# Throttle_Interfaces.net
KiCad netlist of a schematic drawn in Altium Designer
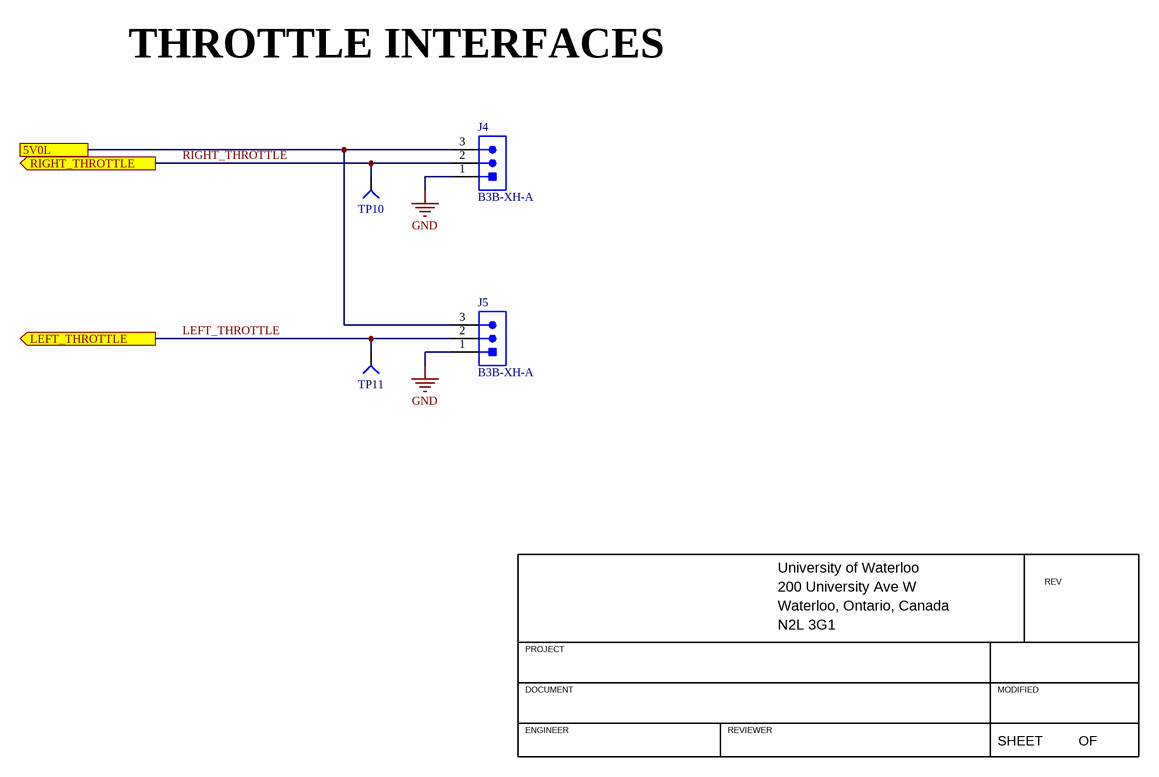
[diagram p0: Throttle Interfaces.SchDoc]

(export (version "E")
  (design (tool "Eeschema 10.0.6"))
  (components
    (comp (ref "J4")
      (value "CON_JST_3POS")
      (footprint "JST_XH_3POS")
      (description "CONN HEADER VERT 3POS 2.5MM")
      (fields (field (name "MANUFACTURER PART NUMBER 1") "B3B-XH-A"))
      (libsource (lib "Personal_Schematic_Library_2022") (part "CON_JST_3POS"))
    )
    (comp (ref "J5")
      (value "CON_JST_3POS")
      (footprint "JST_XH_3POS")
      (description "CONN HEADER VERT 3POS 2.5MM")
      (fields (field (name "MANUFACTURER PART NUMBER 1") "B3B-XH-A"))
      (libsource (lib "Personal_Schematic_Library_2022") (part "CON_JST_3POS"))
    )
    (comp (ref "TP10")
      (value "TESTPOINT_1MM_CIRCLE")
      (footprint "TESTPOINT_CIRCLE_1MM")
      (description "TESTPOINT 1MM CIRCLE")
      (libsource (lib "Personal_Schematic_Library_2022") (part "TESTPOINT_1MM_CIRCLE"))
    )
    (comp (ref "TP11")
      (value "TESTPOINT_1MM_CIRCLE")
      (footprint "TESTPOINT_CIRCLE_1MM")
      (description "TESTPOINT 1MM CIRCLE")
      (libsource (lib "Personal_Schematic_Library_2022") (part "TESTPOINT_1MM_CIRCLE"))
    )
  )
  (nets
    (net (code "1") (name "/5V0L") (class "Default")
      (node (ref "J4") (pin "3") (pinfunction "3_3") (pintype "passive"))
      (node (ref "J5") (pin "3") (pinfunction "3_3") (pintype "passive"))
    )
    (net (code "2") (name "/LEFT_THROTTLE") (class "Default")
      (node (ref "J5") (pin "2") (pinfunction "2_2") (pintype "passive"))
      (node (ref "TP11") (pin "1") (pinfunction "=value_1") (pintype "passive"))
    )
    (net (code "3") (name "/RIGHT_THROTTLE") (class "Default")
      (node (ref "J4") (pin "2") (pinfunction "2_2") (pintype "passive"))
      (node (ref "TP10") (pin "1") (pinfunction "=value_1") (pintype "passive"))
    )
    (net (code "4") (name "GND") (class "Default")
      (node (ref "J4") (pin "1") (pinfunction "1_1") (pintype "passive"))
      (node (ref "J5") (pin "1") (pinfunction "1_1") (pintype "passive"))
    )
  )
)
